# Tag201_Rev4.net
KiCad netlist of a schematic drawn in Altium Designer
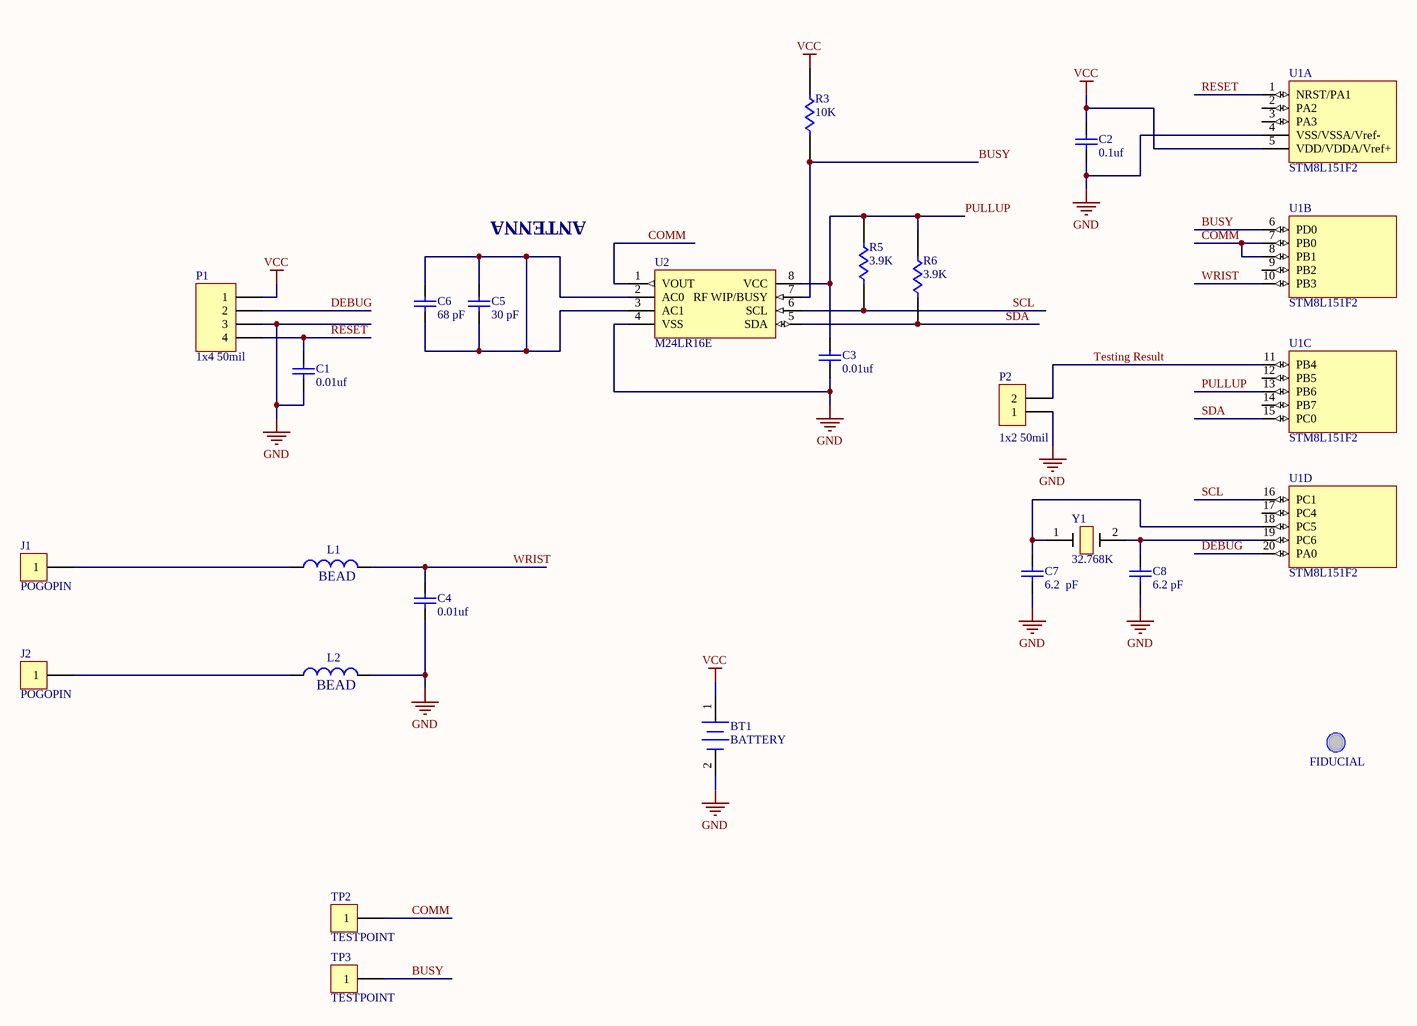
[diagram p0: Tag201_Rev4.SchDoc]

(export (version "E")
  (design (tool "Eeschema 10.0.6"))
  (components
    (comp (ref "BT1")
      (value "BATTERY")
      (footprint "COINCELL2_040912")
      (description "Multicell Battery")
      (fields (field (name "MFG") "MPD") (field (name "PARTNO") "BLP2032SM-GTR"))
      (libsource (lib "Miscellaneous Devices") (part "Battery"))
    )
    (comp (ref "C1")
      (value "0.01uf")
      (footprint "0603_072205")
      (description "Capacitor")
      (fields (field (name "PARTNO") "C1608X7R1E103K"))
      (libsource (lib "Miscellaneous Devices") (part "Cap"))
    )
    (comp (ref "C2")
      (value "0.1uf")
      (footprint "0603_072205")
      (description "Capacitor")
      (fields (field (name "PARTNO") "C1608X7R1C104K"))
      (libsource (lib "Miscellaneous Devices") (part "Cap"))
    )
    (comp (ref "C3")
      (value "0.01uf")
      (footprint "0603_072205")
      (description "Capacitor")
      (fields (field (name "PARTNO") "C1608X7R1E103K"))
      (libsource (lib "Miscellaneous Devices") (part "Cap"))
    )
    (comp (ref "C4")
      (value "0.01uf")
      (footprint "0603_072205")
      (description "Capacitor")
      (fields (field (name "PARTNO") "C1608X7R1E103K"))
      (libsource (lib "Miscellaneous Devices") (part "Cap"))
    )
    (comp (ref "C5")
      (value "30 pF")
      (footprint "0603_072205")
      (description "Capacitor")
      (fields (field (name "PARTNO") "C1608X7R1E103K"))
      (libsource (lib "Miscellaneous Devices") (part "Cap"))
    )
    (comp (ref "C6")
      (value "68 pF")
      (footprint "0603_072205")
      (description "Capacitor")
      (fields (field (name "PARTNO") "C1608X7R1E103K"))
      (libsource (lib "Miscellaneous Devices") (part "Cap"))
    )
    (comp (ref "C7")
      (value "6.2  pF")
      (footprint "0603_072205")
      (description "Capacitor")
      (fields (field (name "PARTNO") "GRM1885C1H6R2DZ01D"))
      (libsource (lib "Miscellaneous Devices") (part "Cap"))
    )
    (comp (ref "C8")
      (value "6.2 pF")
      (footprint "0603_072205")
      (description "Capacitor")
      (fields (field (name "PARTNO") "GRM1885C1H6R2DZ01D"))
      (libsource (lib "Miscellaneous Devices") (part "Cap"))
    )
    (comp (ref "FID1")
      (value "FIDUCIAL")
      (footprint "FiducialTwoSide_020205")
      (libsource (lib "Common") (part "FiducialOneSide040"))
    )
    (comp (ref "J1")
      (value "POGOPIN")
      (footprint "MilMax0910Pad_040912")
      (description "Connector")
      (libsource (lib "Common") (part "CON1"))
    )
    (comp (ref "J2")
      (value "POGOPIN")
      (footprint "MilMax0910Pad_040912")
      (description "Connector")
      (libsource (lib "Common") (part "CON1"))
    )
    (comp (ref "L1")
      (value "BEAD")
      (description "COIL CHOKE 1UH SHIELDED SMD")
      (fields (field (name "MFG") "Murata"))
      (libsource (lib "3PHMotorController") (part "CHOKE RF"))
    )
    (comp (ref "L2")
      (value "BEAD")
      (description "COIL CHOKE 1UH SHIELDED SMD")
      (fields (field (name "MFG") "Murata"))
      (libsource (lib "3PHMotorController") (part "CHOKE RF"))
    )
    (comp (ref "P1")
      (value "1x4 50mil")
      (footprint "1X4 HEADER_50mil_071411")
      (description "Header, 4-Pin")
      (libsource (lib "Miscellaneous Connectors") (part "Header 4"))
    )
    (comp (ref "P2")
      (value "~")
      (footprint "1X2 HEADER_50mil_081611")
      (fields (field (name "ALTIUM_UNNAMED_1") "1x2 50mil"))
      (libsource (lib "Common") (part "CON2"))
    )
    (comp (ref "R3")
      (value "10K")
      (footprint "0603_072205")
      (fields (field (name "PARTNO") "RC0603FR-07100KL"))
      (libsource (lib "Discrete") (part "RESISTOR"))
    )
    (comp (ref "R5")
      (value "3.9K")
      (footprint "0603_072205")
      (fields (field (name "PARTNO") "RC0603FR-0720KL"))
      (libsource (lib "Discrete") (part "RESISTOR"))
    )
    (comp (ref "R6")
      (value "3.9K")
      (footprint "0603_072205")
      (fields (field (name "PARTNO") "RC0603FR-0720KL"))
      (libsource (lib "Discrete") (part "RESISTOR"))
    )
    (comp (ref "TP2")
      (value "TESTPOINT")
      (footprint "TestPoint52x32")
      (description "Connector")
      (libsource (lib "Common") (part "CON1"))
    )
    (comp (ref "TP3")
      (value "TESTPOINT")
      (footprint "TestPoint52x32")
      (description "Connector")
      (libsource (lib "Common") (part "CON1"))
    )
    (comp (ref "U1")
      (value "STM8L151F2")
      (footprint "UFQFPN20ALT_041512")
      (libsource (lib "ActiveWave1") (part "STM8L151F2"))
    )
    (comp (ref "U2")
      (value "M24LR16E")
      (footprint "TSSOP08_022410")
      (libsource (lib "ActiveWave1") (part "M24LR16E"))
    )
    (comp (ref "Y1")
      (value "32.768K")
      (footprint "CRYSTAL32K_3.2mmx1.5mm_040912")
      (libsource (lib "Common") (part "CRYSTAL"))
    )
  )
  (nets
    (net (code "1") (name "/BUSY") (class "Default")
      (node (ref "R3") (pin "2") (pinfunction "2_2") (pintype "passive"))
      (node (ref "TP3") (pin "1") (pinfunction "1_1") (pintype "passive"))
      (node (ref "U1") (pin "6") (pinfunction "PD0_6") (pintype "bidirectional"))
      (node (ref "U2") (pin "7") (pinfunction "RF_WIP/BUSY_7") (pintype "input"))
    )
    (net (code "2") (name "/COMM") (class "Default")
      (node (ref "TP2") (pin "1") (pinfunction "1_1") (pintype "passive"))
      (node (ref "U1") (pin "7") (pinfunction "PB0_7") (pintype "bidirectional"))
      (node (ref "U1") (pin "8") (pinfunction "PB1_8") (pintype "bidirectional"))
      (node (ref "U2") (pin "1") (pinfunction "VOUT_1") (pintype "output"))
    )
    (net (code "3") (name "/DEBUG") (class "Default")
      (node (ref "P1") (pin "2") (pinfunction "2_2") (pintype "passive"))
      (node (ref "U1") (pin "20") (pinfunction "PA0_20") (pintype "bidirectional"))
    )
    (net (code "4") (name "/PULLUP") (class "Default")
      (node (ref "C3") (pin "1") (pinfunction "1_1") (pintype "passive"))
      (node (ref "R5") (pin "1") (pinfunction "1_1") (pintype "passive"))
      (node (ref "R6") (pin "1") (pinfunction "1_1") (pintype "passive"))
      (node (ref "U1") (pin "13") (pinfunction "PB6_13") (pintype "bidirectional"))
      (node (ref "U2") (pin "8") (pinfunction "VCC_8") (pintype "power_in"))
    )
    (net (code "5") (name "/RESET") (class "Default")
      (node (ref "C1") (pin "1") (pinfunction "1_1") (pintype "passive"))
      (node (ref "P1") (pin "4") (pinfunction "4_4") (pintype "passive"))
      (node (ref "U1") (pin "1") (pinfunction "NRST/PA1_1") (pintype "bidirectional"))
    )
    (net (code "6") (name "/SCL") (class "Default")
      (node (ref "R5") (pin "2") (pinfunction "2_2") (pintype "passive"))
      (node (ref "U1") (pin "16") (pinfunction "PC1_16") (pintype "bidirectional"))
      (node (ref "U2") (pin "6") (pinfunction "SCL_6") (pintype "input"))
    )
    (net (code "7") (name "/SDA") (class "Default")
      (node (ref "R6") (pin "2") (pinfunction "2_2") (pintype "passive"))
      (node (ref "U1") (pin "15") (pinfunction "PC0_15") (pintype "bidirectional"))
      (node (ref "U2") (pin "5") (pinfunction "SDA_5") (pintype "bidirectional"))
    )
    (net (code "8") (name "/Testing Result") (class "Default")
      (node (ref "P2") (pin "2") (pinfunction "2_2") (pintype "passive"))
      (node (ref "U1") (pin "11") (pinfunction "PB4_11") (pintype "bidirectional"))
    )
    (net (code "9") (name "/WRIST") (class "Default")
      (node (ref "C4") (pin "1") (pinfunction "1_1") (pintype "passive"))
      (node (ref "L1") (pin "1") (pinfunction "1_1") (pintype "passive"))
      (node (ref "U1") (pin "10") (pinfunction "PB3_10") (pintype "bidirectional"))
    )
    (net (code "10") (name "GND") (class "Default")
      (node (ref "BT1") (pin "2") (pinfunction "-_2") (pintype "passive"))
      (node (ref "C1") (pin "2") (pinfunction "2_2") (pintype "passive"))
      (node (ref "C2") (pin "2") (pinfunction "2_2") (pintype "passive"))
      (node (ref "C3") (pin "2") (pinfunction "2_2") (pintype "passive"))
      (node (ref "C4") (pin "2") (pinfunction "2_2") (pintype "passive"))
      (node (ref "C7") (pin "2") (pinfunction "2_2") (pintype "passive"))
      (node (ref "C8") (pin "2") (pinfunction "2_2") (pintype "passive"))
      (node (ref "L2") (pin "1") (pinfunction "1_1") (pintype "passive"))
      (node (ref "P1") (pin "3") (pinfunction "3_3") (pintype "passive"))
      (node (ref "P2") (pin "1") (pinfunction "1_1") (pintype "passive"))
      (node (ref "U1") (pin "4") (pinfunction "VSS/VSSA/Vref-_4") (pintype "power_in"))
      (node (ref "U2") (pin "4") (pinfunction "VSS_4") (pintype "power_in"))
    )
    (net (code "11") (name "Net-(J1-Pad1)") (class "Default")
      (node (ref "J1") (pin "1") (pinfunction "1_1") (pintype "passive"))
      (node (ref "L1") (pin "2") (pinfunction "2_2") (pintype "passive"))
    )
    (net (code "12") (name "Net-(J2-Pad1)") (class "Default")
      (node (ref "J2") (pin "1") (pinfunction "1_1") (pintype "passive"))
      (node (ref "L2") (pin "2") (pinfunction "2_2") (pintype "passive"))
    )
    (net (code "13") (name "Net-(U1D-PC5)") (class "Default")
      (node (ref "C7") (pin "1") (pinfunction "1_1") (pintype "passive"))
      (node (ref "U1") (pin "18") (pinfunction "PC5_18") (pintype "bidirectional"))
      (node (ref "Y1") (pin "1") (pinfunction "1_1") (pintype "passive"))
    )
    (net (code "14") (name "Net-(U1D-PC6)") (class "Default")
      (node (ref "C8") (pin "1") (pinfunction "1_1") (pintype "passive"))
      (node (ref "U1") (pin "19") (pinfunction "PC6_19") (pintype "bidirectional"))
      (node (ref "Y1") (pin "2") (pinfunction "2_2") (pintype "passive"))
    )
    (net (code "15") (name "Net-(U2-AC0)") (class "Default")
      (node (ref "C5") (pin "1") (pinfunction "1_1") (pintype "passive"))
      (node (ref "C5") (pin "2") (pinfunction "2_2") (pintype "passive"))
      (node (ref "C6") (pin "1") (pinfunction "1_1") (pintype "passive"))
      (node (ref "C6") (pin "2") (pinfunction "2_2") (pintype "passive"))
      (node (ref "U2") (pin "2") (pinfunction "AC0_2") (pintype "passive"))
      (node (ref "U2") (pin "3") (pinfunction "AC1_3") (pintype "passive"))
    )
    (net (code "16") (name "VCC") (class "Default")
      (node (ref "BT1") (pin "1") (pinfunction "+_1") (pintype "passive"))
      (node (ref "C2") (pin "1") (pinfunction "1_1") (pintype "passive"))
      (node (ref "P1") (pin "1") (pinfunction "1_1") (pintype "passive"))
      (node (ref "R3") (pin "1") (pinfunction "1_1") (pintype "passive"))
      (node (ref "U1") (pin "5") (pinfunction "VDD/VDDA/Vref+_5") (pintype "power_in"))
    )
    (net (code "17") (name "unconnected-(FID1-Pad0)") (class "Default")
      (node (ref "FID1") (pin "0") (pinfunction "0_0") (pintype "passive"))
    )
    (net (code "18") (name "unconnected-(U1A-PA2-Pad2)") (class "Default")
      (node (ref "U1") (pin "2") (pinfunction "PA2_2") (pintype "bidirectional"))
    )
    (net (code "19") (name "unconnected-(U1A-PA3-Pad3)") (class "Default")
      (node (ref "U1") (pin "3") (pinfunction "PA3_3") (pintype "bidirectional"))
    )
    (net (code "20") (name "unconnected-(U1B-PB2-Pad9)") (class "Default")
      (node (ref "U1") (pin "9") (pinfunction "PB2_9") (pintype "bidirectional"))
    )
    (net (code "21") (name "unconnected-(U1C-PB5-Pad12)") (class "Default")
      (node (ref "U1") (pin "12") (pinfunction "PB5_12") (pintype "bidirectional"))
    )
    (net (code "22") (name "unconnected-(U1C-PB7-Pad14)") (class "Default")
      (node (ref "U1") (pin "14") (pinfunction "PB7_14") (pintype "bidirectional"))
    )
    (net (code "23") (name "unconnected-(U1D-PC4-Pad17)") (class "Default")
      (node (ref "U1") (pin "17") (pinfunction "PC4_17") (pintype "bidirectional"))
    )
  )
)
